# RFM1262.net
KiCad netlist of a schematic drawn in EAGLE
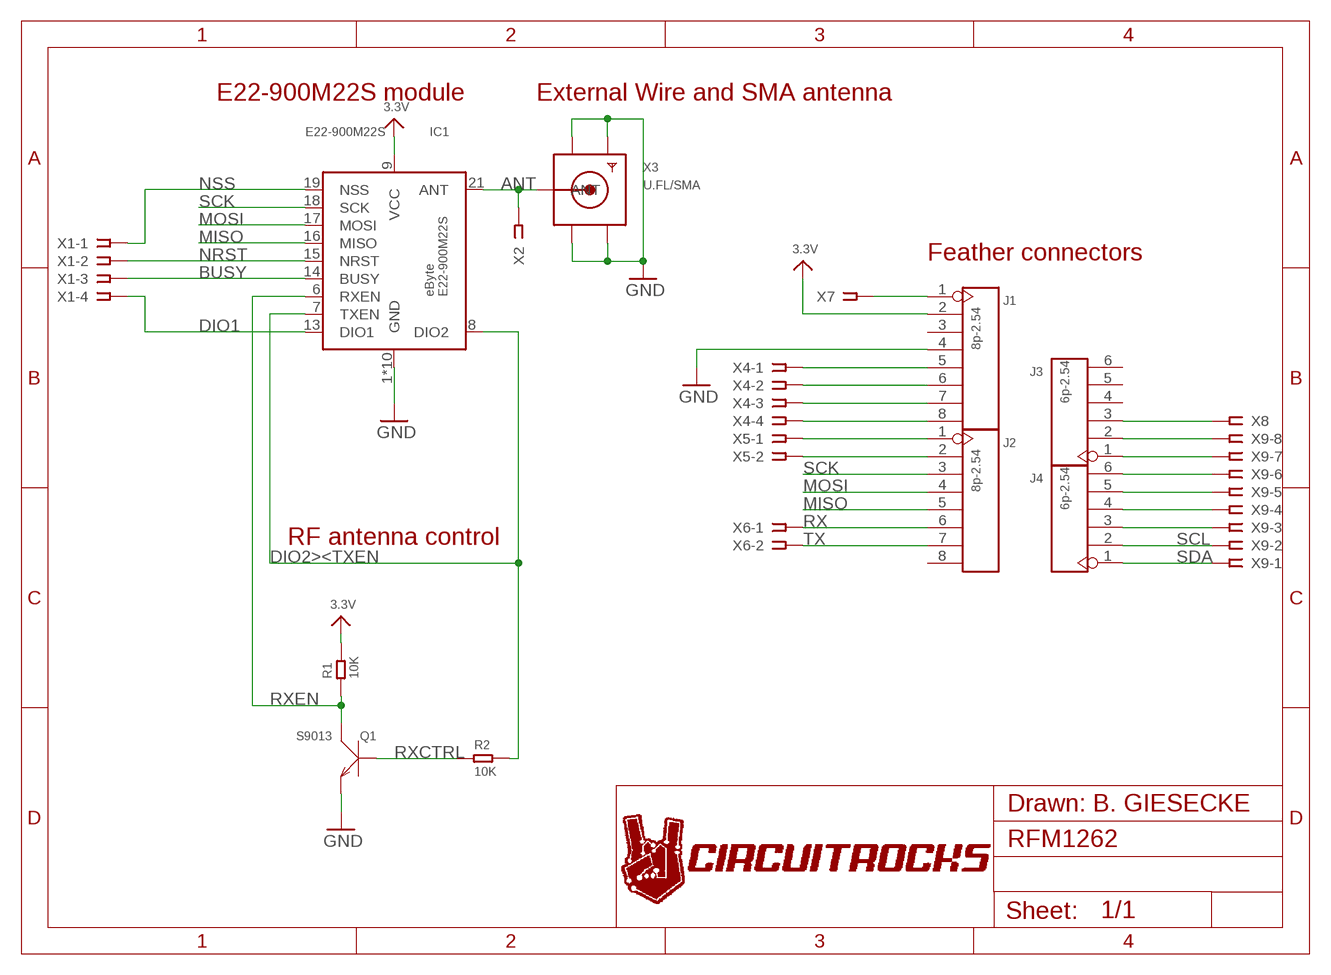
[diagram p0: schematic, sheet 1]

(export (version "E")
  (design (tool "Eeschema 10.0.6"))
  (components
    (comp (ref "IC1")
      (value "E22-900M22S")
      (footprint "eagle-import:E22-900M22S")
      (libsource (lib "eagle-import") (part "E22-900M22S"))
    )
    (comp (ref "J1")
      (value "8p-2.54")
      (footprint "eagle-import:H8-2.54")
      (fields (field (name "MPN") "P125-1108A1BS116A1"))
      (libsource (lib "eagle-import") (part "DIP-BLACK-MALE-HEADER-VERT(8P-2.54)"))
    )
    (comp (ref "J2")
      (value "8p-2.54")
      (footprint "eagle-import:H8-2.54")
      (fields (field (name "MPN") "P125-1108A1BS116A1"))
      (libsource (lib "eagle-import") (part "DIP-BLACK-MALE-HEADER-VERT(8P-2.54)"))
    )
    (comp (ref "J3")
      (value "6p-2.54")
      (footprint "eagle-import:H6-2.54")
      (fields (field (name "MPN") "P125-1106A1BS116A1"))
      (libsource (lib "eagle-import") (part "DIP-BLACK-MALE-HEADER(6P-2.54)"))
    )
    (comp (ref "J4")
      (value "6p-2.54")
      (footprint "eagle-import:H6-2.54")
      (fields (field (name "MPN") "P125-1106A1BS116A1"))
      (libsource (lib "eagle-import") (part "DIP-BLACK-MALE-HEADER(6P-2.54)"))
    )
    (comp (ref "Q1")
      (value "S9013")
      (footprint "eagle-import:SOT-23")
      (libsource (lib "eagle-import") (part "SMD-TRANSISTORS-NPN-25V-500MA-S9013(SOT-23)"))
    )
    (comp (ref "R1")
      (value "10K")
      (footprint "eagle-import:R0805")
      (fields (field (name "MPN") "RC0805FR-0710KL"))
      (libsource (lib "eagle-import") (part "SMD-RES-10K-1%-1/8W(0805)"))
    )
    (comp (ref "R2")
      (value "10K")
      (footprint "eagle-import:R0805")
      (fields (field (name "MPN") "RC0805FR-0710KL"))
      (libsource (lib "eagle-import") (part "SMD-RES-10K-1%-1/8W(0805)"))
    )
    (comp (ref "X1")
      (value "SSW-104-02-G-S")
      (footprint "eagle-import:SSW-104-02-G-S")
      (fields
        (field (name "MF") "Samtec Inc.")
        (field (name "MPN") "SSW-104-02-G-S-RA")
        (field (name "HEIGHT") "0")
      )
      (libsource (lib "eagle-import") (part "SSW-104-02-G-S"))
    )
    (comp (ref "X2")
      (value "SSW-101-02-G-S")
      (footprint "eagle-import:SSW-101-02-G-S")
      (fields (field (name "MF") "Samtec Inc.") (field (name "MPN") "SSW-101-02-G-S-RA"))
      (libsource (lib "eagle-import") (part "SSW-101-02-G-S"))
    )
    (comp (ref "X3")
      (value "U.FL/SMA")
      (footprint "eagle-import:SMA_EDGELAUNCH_UFL")
      (libsource (lib "eagle-import") (part "SMACONNECTOR_EDGE_UFL"))
    )
    (comp (ref "X4")
      (value "SSW-104-02-G-S")
      (footprint "eagle-import:SSW-104-02-G-S")
      (fields
        (field (name "MF") "Samtec Inc.")
        (field (name "MPN") "SSW-104-02-G-S-RA")
        (field (name "HEIGHT") "0")
      )
      (libsource (lib "eagle-import") (part "SSW-104-02-G-S"))
    )
    (comp (ref "X5")
      (value "SSW-102-02-G-S")
      (footprint "eagle-import:SSW-102-02-G-S")
      (fields
        (field (name "MF") "Samtec Inc.")
        (field (name "MPN") "SSW-102-02-G-S-RA")
        (field (name "HEIGHT") "0")
      )
      (libsource (lib "eagle-import") (part "SSW-102-02-G-S"))
    )
    (comp (ref "X6")
      (value "SSW-102-02-G-S")
      (footprint "eagle-import:SSW-102-02-G-S")
      (fields
        (field (name "MF") "Samtec Inc.")
        (field (name "MPN") "SSW-102-02-G-S-RA")
        (field (name "HEIGHT") "0")
      )
      (libsource (lib "eagle-import") (part "SSW-102-02-G-S"))
    )
    (comp (ref "X7")
      (value "SSW-101-02-G-S")
      (footprint "eagle-import:SSW-101-02-G-S")
      (fields (field (name "MF") "Samtec Inc.") (field (name "MPN") "SSW-101-02-G-S-RA"))
      (libsource (lib "eagle-import") (part "SSW-101-02-G-S"))
    )
    (comp (ref "X8")
      (value "SSW-101-02-G-S")
      (footprint "eagle-import:SSW-101-02-G-S")
      (fields (field (name "MF") "Samtec Inc.") (field (name "MPN") "SSW-101-02-G-S-RA"))
      (libsource (lib "eagle-import") (part "SSW-101-02-G-S"))
    )
    (comp (ref "X9")
      (value "SSW-108-02-G-S")
      (footprint "eagle-import:SSW-108-02-G-S")
      (fields
        (field (name "MF") "Samtec Inc.")
        (field (name "MPN") "SSW-108-02-G-S-RA")
        (field (name "HEIGHT") "0")
      )
      (libsource (lib "eagle-import") (part "SSW-108-02-G-S"))
    )
  )
  (nets
    (net (code "1") (name "/ANT") (class "Default")
      (node (ref "IC1") (pin "21") (pinfunction "ANT_21") (pintype "output"))
      (node (ref "X2") (pin "1") (pinfunction "1_1") (pintype "passive"))
      (node (ref "X3") (pin "P") (pinfunction "ANT_P") (pintype "bidirectional"))
    )
    (net (code "2") (name "/BUSY") (class "Default")
      (node (ref "IC1") (pin "14") (pinfunction "BUSY_14") (pintype "bidirectional"))
      (node (ref "X1") (pin "3") (pinfunction "1_3") (pintype "passive"))
    )
    (net (code "3") (name "/DIO1") (class "Default")
      (node (ref "IC1") (pin "13") (pinfunction "DIO1_13") (pintype "bidirectional"))
      (node (ref "X1") (pin "4") (pinfunction "1_4") (pintype "passive"))
    )
    (net (code "4") (name "/DIO2><TXEN") (class "Default")
      (node (ref "IC1") (pin "7") (pinfunction "TXEN_7") (pintype "bidirectional"))
      (node (ref "IC1") (pin "8") (pinfunction "DIO2_8") (pintype "bidirectional"))
      (node (ref "R2") (pin "2") (pinfunction "2_2") (pintype "passive"))
    )
    (net (code "5") (name "/MISO") (class "Default")
      (node (ref "IC1") (pin "16") (pinfunction "MISO_16") (pintype "bidirectional"))
      (node (ref "J2") (pin "5") (pinfunction "5_5") (pintype "bidirectional"))
    )
    (net (code "6") (name "/MOSI") (class "Default")
      (node (ref "IC1") (pin "17") (pinfunction "MOSI_17") (pintype "bidirectional"))
      (node (ref "J2") (pin "4") (pinfunction "4_4") (pintype "bidirectional"))
    )
    (net (code "7") (name "/NRST") (class "Default")
      (node (ref "IC1") (pin "15") (pinfunction "NRST_15") (pintype "bidirectional"))
      (node (ref "X1") (pin "2") (pinfunction "1_2") (pintype "passive"))
    )
    (net (code "8") (name "/NSS") (class "Default")
      (node (ref "IC1") (pin "19") (pinfunction "NSS_19") (pintype "input"))
      (node (ref "X1") (pin "1") (pinfunction "1_1") (pintype "passive"))
    )
    (net (code "9") (name "/RX") (class "Default")
      (node (ref "J2") (pin "6") (pinfunction "6_6") (pintype "bidirectional"))
      (node (ref "X6") (pin "1") (pinfunction "1_1") (pintype "passive"))
    )
    (net (code "10") (name "/RXCTRL") (class "Default")
      (node (ref "Q1") (pin "1") (pinfunction "B_1") (pintype "passive"))
      (node (ref "R2") (pin "1") (pinfunction "1_1") (pintype "passive"))
    )
    (net (code "11") (name "/RXEN") (class "Default")
      (node (ref "IC1") (pin "6") (pinfunction "RXEN_6") (pintype "input"))
      (node (ref "Q1") (pin "3") (pinfunction "C_3") (pintype "passive"))
      (node (ref "R1") (pin "1") (pinfunction "1_1") (pintype "passive"))
    )
    (net (code "12") (name "/SCK") (class "Default")
      (node (ref "IC1") (pin "18") (pinfunction "SCK_18") (pintype "input"))
      (node (ref "J2") (pin "3") (pinfunction "3_3") (pintype "bidirectional"))
    )
    (net (code "13") (name "/SCL") (class "Default")
      (node (ref "J4") (pin "2") (pinfunction "2_2") (pintype "bidirectional"))
      (node (ref "X9") (pin "2") (pinfunction "1_2") (pintype "passive"))
    )
    (net (code "14") (name "/SDA") (class "Default")
      (node (ref "J4") (pin "1") (pinfunction "1_1") (pintype "bidirectional"))
      (node (ref "X9") (pin "1") (pinfunction "1_1") (pintype "passive"))
    )
    (net (code "15") (name "/TX") (class "Default")
      (node (ref "J2") (pin "7") (pinfunction "7_7") (pintype "bidirectional"))
      (node (ref "X6") (pin "2") (pinfunction "1_2") (pintype "passive"))
    )
    (net (code "16") (name "3.3V") (class "Default")
      (node (ref "IC1") (pin "9") (pinfunction "VCC_9") (pintype "power_in"))
      (node (ref "J1") (pin "2") (pinfunction "2_2") (pintype "bidirectional"))
      (node (ref "R1") (pin "2") (pinfunction "2_2") (pintype "passive"))
    )
    (net (code "17") (name "GND") (class "Default")
      (node (ref "IC1") (pin "1") (pinfunction "GND_1") (pintype "power_in"))
      (node (ref "IC1") (pin "10") (pinfunction "GND_10") (pintype "power_in"))
      (node (ref "IC1") (pin "11") (pinfunction "GND_11") (pintype "power_in"))
      (node (ref "IC1") (pin "12") (pinfunction "GND_12") (pintype "power_in"))
      (node (ref "IC1") (pin "2") (pinfunction "GND_2") (pintype "power_in"))
      (node (ref "IC1") (pin "20") (pinfunction "GND_20") (pintype "power_in"))
      (node (ref "IC1") (pin "22") (pinfunction "GND_22") (pintype "power_in"))
      (node (ref "IC1") (pin "3") (pinfunction "GND_3") (pintype "power_in"))
      (node (ref "IC1") (pin "4") (pinfunction "GND_4") (pintype "power_in"))
      (node (ref "IC1") (pin "5") (pinfunction "GND_5") (pintype "power_in"))
      (node (ref "J1") (pin "4") (pinfunction "4_4") (pintype "bidirectional"))
      (node (ref "Q1") (pin "2") (pinfunction "E_2") (pintype "passive"))
      (node (ref "X3") (pin "GND@1") (pinfunction "GND1_GND@1") (pintype "power_in"))
      (node (ref "X3") (pin "GND@2") (pinfunction "GND2_GND@2") (pintype "power_in"))
      (node (ref "X3") (pin "GND@3") (pinfunction "GND3_GND@3") (pintype "power_in"))
      (node (ref "X3") (pin "GND@4") (pinfunction "GND4_GND@4") (pintype "power_in"))
    )
    (net (code "18") (name "Net-(J1-Pad1)") (class "Default")
      (node (ref "J1") (pin "1") (pinfunction "1_1") (pintype "bidirectional"))
      (node (ref "X7") (pin "1") (pinfunction "1_1") (pintype "passive"))
    )
    (net (code "19") (name "Net-(J1-Pad5)") (class "Default")
      (node (ref "J1") (pin "5") (pinfunction "5_5") (pintype "bidirectional"))
      (node (ref "X4") (pin "1") (pinfunction "1_1") (pintype "passive"))
    )
    (net (code "20") (name "Net-(J2-Pad1)") (class "Default")
      (node (ref "J2") (pin "1") (pinfunction "1_1") (pintype "bidirectional"))
      (node (ref "X5") (pin "1") (pinfunction "1_1") (pintype "passive"))
    )
    (net (code "21") (name "Net-(J3-Pad3)") (class "Default")
      (node (ref "J3") (pin "3") (pinfunction "3_3") (pintype "bidirectional"))
      (node (ref "X8") (pin "1") (pinfunction "1_1") (pintype "passive"))
    )
    (net (code "22") (name "Net-(X4B-1)") (class "Default")
      (node (ref "J1") (pin "6") (pinfunction "6_6") (pintype "bidirectional"))
      (node (ref "X4") (pin "2") (pinfunction "1_2") (pintype "passive"))
    )
    (net (code "23") (name "Net-(X4C-1)") (class "Default")
      (node (ref "J1") (pin "7") (pinfunction "7_7") (pintype "bidirectional"))
      (node (ref "X4") (pin "3") (pinfunction "1_3") (pintype "passive"))
    )
    (net (code "24") (name "Net-(X4D-1)") (class "Default")
      (node (ref "J1") (pin "8") (pinfunction "8_8") (pintype "bidirectional"))
      (node (ref "X4") (pin "4") (pinfunction "1_4") (pintype "passive"))
    )
    (net (code "25") (name "Net-(X5B-1)") (class "Default")
      (node (ref "J2") (pin "2") (pinfunction "2_2") (pintype "bidirectional"))
      (node (ref "X5") (pin "2") (pinfunction "1_2") (pintype "passive"))
    )
    (net (code "26") (name "Net-(X9C-1)") (class "Default")
      (node (ref "J4") (pin "3") (pinfunction "3_3") (pintype "bidirectional"))
      (node (ref "X9") (pin "3") (pinfunction "1_3") (pintype "passive"))
    )
    (net (code "27") (name "Net-(X9D-1)") (class "Default")
      (node (ref "J4") (pin "4") (pinfunction "4_4") (pintype "bidirectional"))
      (node (ref "X9") (pin "4") (pinfunction "1_4") (pintype "passive"))
    )
    (net (code "28") (name "Net-(X9E-1)") (class "Default")
      (node (ref "J4") (pin "5") (pinfunction "5_5") (pintype "bidirectional"))
      (node (ref "X9") (pin "5") (pinfunction "1_5") (pintype "passive"))
    )
    (net (code "29") (name "Net-(X9F-1)") (class "Default")
      (node (ref "J4") (pin "6") (pinfunction "6_6") (pintype "bidirectional"))
      (node (ref "X9") (pin "6") (pinfunction "1_6") (pintype "passive"))
    )
    (net (code "30") (name "Net-(X9G-1)") (class "Default")
      (node (ref "J3") (pin "1") (pinfunction "1_1") (pintype "bidirectional"))
      (node (ref "X9") (pin "7") (pinfunction "1_7") (pintype "passive"))
    )
    (net (code "31") (name "Net-(X9H-1)") (class "Default")
      (node (ref "J3") (pin "2") (pinfunction "2_2") (pintype "bidirectional"))
      (node (ref "X9") (pin "8") (pinfunction "1_8") (pintype "passive"))
    )
    (net (code "32") (name "unconnected-(J1-Pad3)") (class "Default")
      (node (ref "J1") (pin "3") (pinfunction "3_3") (pintype "bidirectional"))
    )
    (net (code "33") (name "unconnected-(J2-Pad8)") (class "Default")
      (node (ref "J2") (pin "8") (pinfunction "8_8") (pintype "bidirectional"))
    )
    (net (code "34") (name "unconnected-(J3-Pad4)") (class "Default")
      (node (ref "J3") (pin "4") (pinfunction "4_4") (pintype "bidirectional"))
    )
    (net (code "35") (name "unconnected-(J3-Pad5)") (class "Default")
      (node (ref "J3") (pin "5") (pinfunction "5_5") (pintype "bidirectional"))
    )
    (net (code "36") (name "unconnected-(J3-Pad6)") (class "Default")
      (node (ref "J3") (pin "6") (pinfunction "6_6") (pintype "bidirectional"))
    )
  )
)
